# ECAT_RJ45.net
KiCad netlist of a schematic drawn in Altium Designer
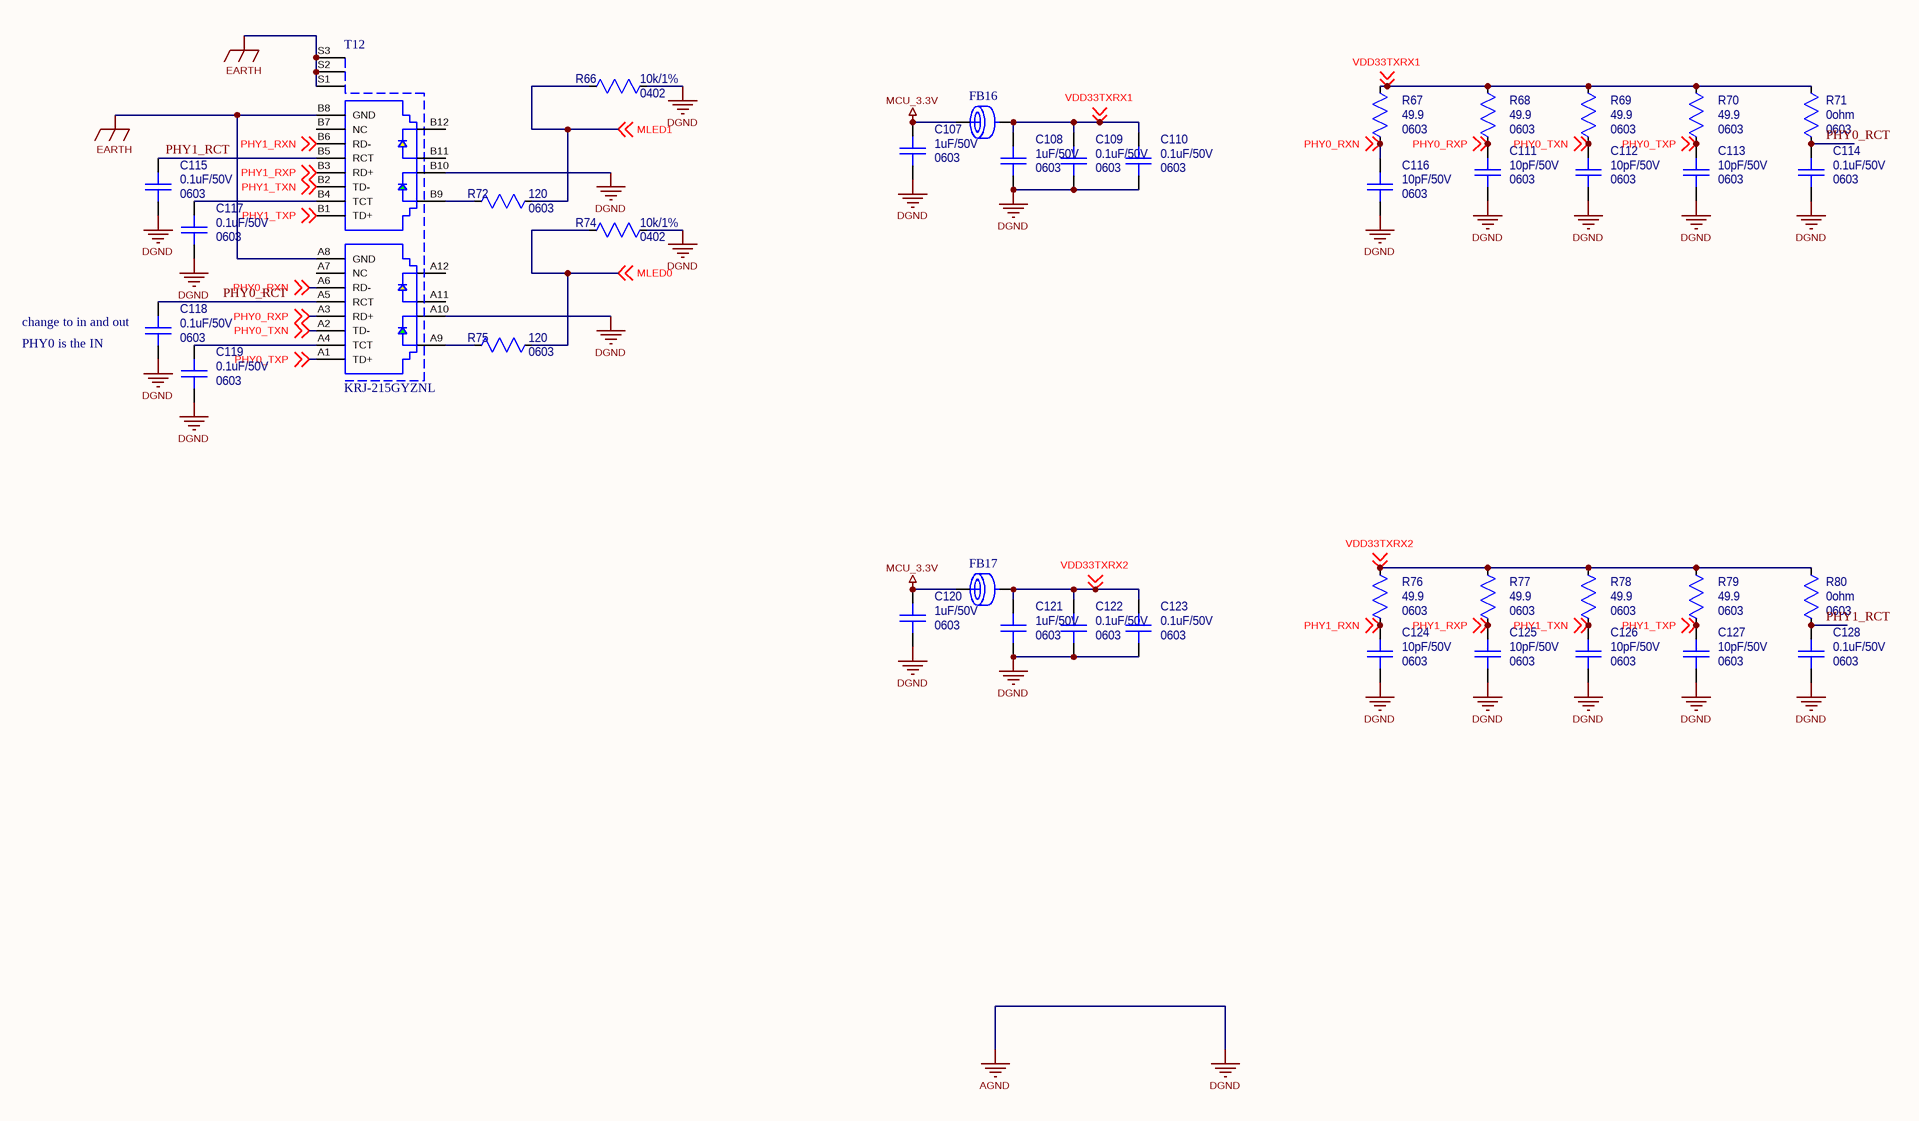
[diagram p0: ECAT RJ45.SchDoc]

(export (version "E")
  (design (tool "Eeschema 10.0.6"))
  (components
    (comp (ref "C107")
      (value "1uF/50V")
      (footprint "CAPC1608X092N_0603")
      (fields
        (field (name "PARTNUMBER") "CL10A105KB8NNNC")
        (field (name "TOLERANCE") "[tol]")
        (field (name "PACKAGE") "0603")
      )
      (libsource (lib "Karl") (part "Capacitor_0603"))
    )
    (comp (ref "C108")
      (value "1uF/50V")
      (footprint "CAPC1608X092N_0603")
      (fields
        (field (name "PARTNUMBER") "CL10A105KB8NNNC")
        (field (name "TOLERANCE") "[tol]")
        (field (name "PACKAGE") "0603")
      )
      (libsource (lib "Karl") (part "Capacitor_0603"))
    )
    (comp (ref "C109")
      (value "0.1uF/50V")
      (footprint "CAPC1608X092N_0603")
      (fields
        (field (name "PARTNUMBER") "CC0603KRX7R9BB104")
        (field (name "TOLERANCE") "[tol]")
        (field (name "PACKAGE") "0603")
      )
      (libsource (lib "Karl") (part "Capacitor_0402"))
    )
    (comp (ref "C110")
      (value "0.1uF/50V")
      (footprint "CAPC1608X092N_0603")
      (fields
        (field (name "PARTNUMBER") "CC0603KRX7R9BB104")
        (field (name "TOLERANCE") "[tol]")
        (field (name "PACKAGE") "0603")
      )
      (libsource (lib "Karl") (part "Capacitor_0402"))
    )
    (comp (ref "C111")
      (value "10pF/50V")
      (footprint "CAPC1608X092N_0603")
      (fields
        (field (name "PARTNUMBER") "CC0603JRNPO9BN100")
        (field (name "TOLERANCE") "[tol]")
        (field (name "PACKAGE") "0603")
      )
      (libsource (lib "Karl") (part "Capacitor_0603"))
    )
    (comp (ref "C112")
      (value "10pF/50V")
      (footprint "CAPC1608X092N_0603")
      (fields
        (field (name "PARTNUMBER") "CC0603JRNPO9BN100")
        (field (name "TOLERANCE") "[tol]")
        (field (name "PACKAGE") "0603")
      )
      (libsource (lib "Karl") (part "Capacitor_0603"))
    )
    (comp (ref "C113")
      (value "10pF/50V")
      (footprint "CAPC1608X092N_0603")
      (fields
        (field (name "PARTNUMBER") "CC0603JRNPO9BN100")
        (field (name "TOLERANCE") "[tol]")
        (field (name "PACKAGE") "0603")
      )
      (libsource (lib "Karl") (part "Capacitor_0603"))
    )
    (comp (ref "C114")
      (value "0.1uF/50V")
      (footprint "CAPC1608X092N_0603")
      (fields
        (field (name "PARTNUMBER") "CC0603KRX7R9BB104")
        (field (name "TOLERANCE") "[tol]")
        (field (name "PACKAGE") "0603")
      )
      (libsource (lib "Karl") (part "Capacitor_0402"))
    )
    (comp (ref "C115")
      (value "0.1uF/50V")
      (footprint "CAPC1608X092N_0603")
      (fields
        (field (name "PARTNUMBER") "CC0603KRX7R9BB104")
        (field (name "TOLERANCE") "[tol]")
        (field (name "PACKAGE") "0603")
      )
      (libsource (lib "Karl") (part "Capacitor_0603"))
    )
    (comp (ref "C116")
      (value "10pF/50V")
      (footprint "CAPC1608X092N_0603")
      (fields
        (field (name "PARTNUMBER") "CC0603JRNPO9BN100")
        (field (name "TOLERANCE") "[tol]")
        (field (name "PACKAGE") "0603")
      )
      (libsource (lib "Karl") (part "Capacitor_0603"))
    )
    (comp (ref "C117")
      (value "0.1uF/50V")
      (footprint "CAPC1608X092N_0603")
      (fields
        (field (name "PARTNUMBER") "CC0603KRX7R9BB104")
        (field (name "TOLERANCE") "[tol]")
        (field (name "PACKAGE") "0603")
      )
      (libsource (lib "Karl") (part "Capacitor_0603"))
    )
    (comp (ref "C118")
      (value "0.1uF/50V")
      (footprint "CAPC1608X092N_0603")
      (fields
        (field (name "PARTNUMBER") "CC0603KRX7R9BB104")
        (field (name "TOLERANCE") "[tol]")
        (field (name "PACKAGE") "0603")
      )
      (libsource (lib "Karl") (part "Capacitor_0603"))
    )
    (comp (ref "C119")
      (value "0.1uF/50V")
      (footprint "CAPC1608X092N_0603")
      (fields
        (field (name "PARTNUMBER") "CC0603KRX7R9BB104")
        (field (name "TOLERANCE") "[tol]")
        (field (name "PACKAGE") "0603")
      )
      (libsource (lib "Karl") (part "Capacitor_0603"))
    )
    (comp (ref "C120")
      (value "1uF/50V")
      (footprint "CAPC1608X092N_0603")
      (fields
        (field (name "PARTNUMBER") "CL10A105KB8NNNC")
        (field (name "TOLERANCE") "[tol]")
        (field (name "PACKAGE") "0603")
      )
      (libsource (lib "Karl") (part "Capacitor_0603"))
    )
    (comp (ref "C121")
      (value "1uF/50V")
      (footprint "CAPC1608X092N_0603")
      (fields
        (field (name "PARTNUMBER") "CL10A105KB8NNNC")
        (field (name "TOLERANCE") "[tol]")
        (field (name "PACKAGE") "0603")
      )
      (libsource (lib "Karl") (part "Capacitor_0603"))
    )
    (comp (ref "C122")
      (value "0.1uF/50V")
      (footprint "CAPC1608X092N_0603")
      (fields
        (field (name "PARTNUMBER") "CC0603KRX7R9BB104")
        (field (name "TOLERANCE") "[tol]")
        (field (name "PACKAGE") "0603")
      )
      (libsource (lib "Karl") (part "Capacitor_0402"))
    )
    (comp (ref "C123")
      (value "0.1uF/50V")
      (footprint "CAPC1608X092N_0603")
      (fields
        (field (name "PARTNUMBER") "CC0603KRX7R9BB104")
        (field (name "TOLERANCE") "[tol]")
        (field (name "PACKAGE") "0603")
      )
      (libsource (lib "Karl") (part "Capacitor_0402"))
    )
    (comp (ref "C124")
      (value "10pF/50V")
      (footprint "CAPC1608X092N_0603")
      (fields
        (field (name "PARTNUMBER") "CC0603JRNPO9BN100")
        (field (name "TOLERANCE") "[tol]")
        (field (name "PACKAGE") "0603")
      )
      (libsource (lib "Karl") (part "Capacitor_0603"))
    )
    (comp (ref "C125")
      (value "10pF/50V")
      (footprint "CAPC1608X092N_0603")
      (fields
        (field (name "PARTNUMBER") "CC0603JRNPO9BN100")
        (field (name "TOLERANCE") "[tol]")
        (field (name "PACKAGE") "0603")
      )
      (libsource (lib "Karl") (part "Capacitor_0603"))
    )
    (comp (ref "C126")
      (value "10pF/50V")
      (footprint "CAPC1608X092N_0603")
      (fields
        (field (name "PARTNUMBER") "CC0603JRNPO9BN100")
        (field (name "TOLERANCE") "[tol]")
        (field (name "PACKAGE") "0603")
      )
      (libsource (lib "Karl") (part "Capacitor_0603"))
    )
    (comp (ref "C127")
      (value "10pF/50V")
      (footprint "CAPC1608X092N_0603")
      (fields
        (field (name "PARTNUMBER") "CC0603JRNPO9BN100")
        (field (name "TOLERANCE") "[tol]")
        (field (name "PACKAGE") "0603")
      )
      (libsource (lib "Karl") (part "Capacitor_0603"))
    )
    (comp (ref "C128")
      (value "0.1uF/50V")
      (footprint "CAPC1608X092N_0603")
      (fields
        (field (name "PARTNUMBER") "CC0603KRX7R9BB104")
        (field (name "TOLERANCE") "[tol]")
        (field (name "PACKAGE") "0603")
      )
      (libsource (lib "Karl") (part "Capacitor_0402"))
    )
    (comp (ref "FB16")
      (value "FBC0603")
      (footprint "FBC0603")
      (fields (field (name "PARTNUMBER") "BLM18AG601SN1D"))
      (libsource (lib "Karl") (part "FBC0603"))
    )
    (comp (ref "FB17")
      (value "FBC0603")
      (footprint "FBC0603")
      (fields (field (name "PARTNUMBER") "BLM18AG601SN1D"))
      (libsource (lib "Karl") (part "FBC0603"))
    )
    (comp (ref "R66")
      (value "10k/1%")
      (footprint "RESC1005X040N_0402")
      (fields
        (field (name "PARTNUMBER") "MR04X1002FTL")
        (field (name "TOLERANCE") "tol")
        (field (name "PACKAGE") "0402")
      )
      (libsource (lib "Karl") (part "Resistor_0402"))
    )
    (comp (ref "R67")
      (value "49.9")
      (footprint "RESC1608X055N_0603")
      (fields
        (field (name "PARTNUMBER") "0603WAF499JT5E")
        (field (name "TOLERANCE") "tol")
        (field (name "PACKAGE") "0603")
      )
      (libsource (lib "Karl") (part "Resistor_0603"))
    )
    (comp (ref "R68")
      (value "49.9")
      (footprint "RESC1608X055N_0603")
      (fields
        (field (name "PARTNUMBER") "0603WAF499JT5E")
        (field (name "TOLERANCE") "tol")
        (field (name "PACKAGE") "0603")
      )
      (libsource (lib "Karl") (part "Resistor_0603"))
    )
    (comp (ref "R69")
      (value "49.9")
      (footprint "RESC1608X055N_0603")
      (fields
        (field (name "PARTNUMBER") "0603WAF499JT5E")
        (field (name "TOLERANCE") "tol")
        (field (name "PACKAGE") "0603")
      )
      (libsource (lib "Karl") (part "Resistor_0603"))
    )
    (comp (ref "R70")
      (value "49.9")
      (footprint "RESC1608X055N_0603")
      (fields
        (field (name "PARTNUMBER") "0603WAF499JT5E")
        (field (name "TOLERANCE") "tol")
        (field (name "PACKAGE") "0603")
      )
      (libsource (lib "Karl") (part "Resistor_0603"))
    )
    (comp (ref "R71")
      (value "0ohm")
      (footprint "RESC1608X055N_0603")
      (fields
        (field (name "PARTNUMBER") "RC0603JR-070RL")
        (field (name "TOLERANCE") "tol")
        (field (name "PACKAGE") "0603")
      )
      (libsource (lib "Karl") (part "Resistor_0603"))
    )
    (comp (ref "R72")
      (value "120")
      (footprint "RESC1608X055N_0603")
      (fields
        (field (name "PARTNUMBER") "RC0603FR-07120RL")
        (field (name "TOLERANCE") "tol")
        (field (name "PACKAGE") "0603")
      )
      (libsource (lib "Karl") (part "Resistor_0603"))
    )
    (comp (ref "R74")
      (value "10k/1%")
      (footprint "RESC1005X040N_0402")
      (fields
        (field (name "PARTNUMBER") "MR04X1002FTL")
        (field (name "TOLERANCE") "tol")
        (field (name "PACKAGE") "0402")
      )
      (libsource (lib "Karl") (part "Resistor_0402"))
    )
    (comp (ref "R75")
      (value "120")
      (footprint "RESC1608X055N_0603")
      (fields
        (field (name "PARTNUMBER") "RC0603FR-07120RL")
        (field (name "TOLERANCE") "tol")
        (field (name "PACKAGE") "0603")
      )
      (libsource (lib "Karl") (part "Resistor_0603"))
    )
    (comp (ref "R76")
      (value "49.9")
      (footprint "RESC1608X055N_0603")
      (fields
        (field (name "PARTNUMBER") "0603WAF499JT5E")
        (field (name "TOLERANCE") "tol")
        (field (name "PACKAGE") "0603")
      )
      (libsource (lib "Karl") (part "Resistor_0603"))
    )
    (comp (ref "R77")
      (value "49.9")
      (footprint "RESC1608X055N_0603")
      (fields
        (field (name "PARTNUMBER") "0603WAF499JT5E")
        (field (name "TOLERANCE") "tol")
        (field (name "PACKAGE") "0603")
      )
      (libsource (lib "Karl") (part "Resistor_0603"))
    )
    (comp (ref "R78")
      (value "49.9")
      (footprint "RESC1608X055N_0603")
      (fields
        (field (name "PARTNUMBER") "0603WAF499JT5E")
        (field (name "TOLERANCE") "tol")
        (field (name "PACKAGE") "0603")
      )
      (libsource (lib "Karl") (part "Resistor_0603"))
    )
    (comp (ref "R79")
      (value "49.9")
      (footprint "RESC1608X055N_0603")
      (fields
        (field (name "PARTNUMBER") "0603WAF499JT5E")
        (field (name "TOLERANCE") "tol")
        (field (name "PACKAGE") "0603")
      )
      (libsource (lib "Karl") (part "Resistor_0603"))
    )
    (comp (ref "R80")
      (value "0ohm")
      (footprint "RESC1608X055N_0603")
      (fields
        (field (name "PARTNUMBER") "RC0603JR-070RL")
        (field (name "TOLERANCE") "tol")
        (field (name "PACKAGE") "0603")
      )
      (libsource (lib "Karl") (part "Resistor_0603"))
    )
    (comp (ref "T12")
      (value "KRJ-215GYZNL")
      (footprint "DGKYD-KRJ-211_V")
      (fields (field (name "PART NUMBER") "KRJ-211GYNL") (field (name "PUBLISHER") "DGKYD"))
      (libsource (lib "Bogen") (part "KRJ-215GYZNL"))
    )
  )
  (nets
    (net (code "1") (name "/PHY0_RCT") (class "Default")
      (node (ref "C114") (pin "1") (pinfunction "1_1") (pintype "passive"))
      (node (ref "C118") (pin "1") (pinfunction "1_1") (pintype "passive"))
      (node (ref "R71") (pin "2") (pinfunction "2_2") (pintype "passive"))
      (node (ref "T12") (pin "A5") (pinfunction "RCT_A5") (pintype "passive"))
    )
    (net (code "2") (name "/PHY1_RCT") (class "Default")
      (node (ref "C115") (pin "1") (pinfunction "1_1") (pintype "passive"))
      (node (ref "C128") (pin "1") (pinfunction "1_1") (pintype "passive"))
      (node (ref "R80") (pin "2") (pinfunction "2_2") (pintype "passive"))
      (node (ref "T12") (pin "B5") (pinfunction "RCT_B5") (pintype "passive"))
    )
    (net (code "3") (name "AGND") (class "Default")
      (node (ref "C107") (pin "2") (pinfunction "2_2") (pintype "passive"))
      (node (ref "C108") (pin "2") (pinfunction "2_2") (pintype "passive"))
      (node (ref "C109") (pin "2") (pinfunction "2_2") (pintype "passive"))
      (node (ref "C110") (pin "2") (pinfunction "2_2") (pintype "passive"))
      (node (ref "C111") (pin "2") (pinfunction "2_2") (pintype "passive"))
      (node (ref "C112") (pin "2") (pinfunction "2_2") (pintype "passive"))
      (node (ref "C113") (pin "2") (pinfunction "2_2") (pintype "passive"))
      (node (ref "C114") (pin "2") (pinfunction "2_2") (pintype "passive"))
      (node (ref "C115") (pin "2") (pinfunction "2_2") (pintype "passive"))
      (node (ref "C116") (pin "2") (pinfunction "2_2") (pintype "passive"))
      (node (ref "C117") (pin "2") (pinfunction "2_2") (pintype "passive"))
      (node (ref "C118") (pin "2") (pinfunction "2_2") (pintype "passive"))
      (node (ref "C119") (pin "2") (pinfunction "2_2") (pintype "passive"))
      (node (ref "C120") (pin "2") (pinfunction "2_2") (pintype "passive"))
      (node (ref "C121") (pin "2") (pinfunction "2_2") (pintype "passive"))
      (node (ref "C122") (pin "2") (pinfunction "2_2") (pintype "passive"))
      (node (ref "C123") (pin "2") (pinfunction "2_2") (pintype "passive"))
      (node (ref "C124") (pin "2") (pinfunction "2_2") (pintype "passive"))
      (node (ref "C125") (pin "2") (pinfunction "2_2") (pintype "passive"))
      (node (ref "C126") (pin "2") (pinfunction "2_2") (pintype "passive"))
      (node (ref "C127") (pin "2") (pinfunction "2_2") (pintype "passive"))
      (node (ref "C128") (pin "2") (pinfunction "2_2") (pintype "passive"))
      (node (ref "R66") (pin "1") (pinfunction "1_1") (pintype "passive"))
      (node (ref "R74") (pin "1") (pinfunction "1_1") (pintype "passive"))
      (node (ref "T12") (pin "A10") (pinfunction "A10_A10") (pintype "passive"))
      (node (ref "T12") (pin "B10") (pinfunction "B10_B10") (pintype "passive"))
    )
    (net (code "4") (name "EARTH") (class "Default")
      (node (ref "T12") (pin "A8") (pinfunction "GND_A8") (pintype "passive"))
      (node (ref "T12") (pin "B8") (pinfunction "GND_B8") (pintype "passive"))
      (node (ref "T12") (pin "S1") (pinfunction "Shield_S1") (pintype "passive"))
      (node (ref "T12") (pin "S2") (pinfunction "Shield_S2") (pintype "passive"))
      (node (ref "T12") (pin "S3") (pinfunction "Shield_S3") (pintype "passive"))
    )
    (net (code "5") (name "MCU_3.3V") (class "Default")
      (node (ref "C107") (pin "1") (pinfunction "1_1") (pintype "passive"))
      (node (ref "C120") (pin "1") (pinfunction "1_1") (pintype "passive"))
      (node (ref "FB16") (pin "1") (pinfunction "1_1") (pintype "passive"))
      (node (ref "FB17") (pin "1") (pinfunction "1_1") (pintype "passive"))
    )
    (net (code "6") (name "MLED0") (class "Default")
      (node (ref "R74") (pin "2") (pinfunction "2_2") (pintype "passive"))
      (node (ref "R75") (pin "1") (pinfunction "1_1") (pintype "passive"))
    )
    (net (code "7") (name "MLED1") (class "Default")
      (node (ref "R66") (pin "2") (pinfunction "2_2") (pintype "passive"))
      (node (ref "R72") (pin "1") (pinfunction "1_1") (pintype "passive"))
    )
    (net (code "8") (name "Net-(C117-Pad1)") (class "Default")
      (node (ref "C117") (pin "1") (pinfunction "1_1") (pintype "passive"))
      (node (ref "T12") (pin "B4") (pinfunction "TCT_B4") (pintype "passive"))
    )
    (net (code "9") (name "Net-(C119-Pad1)") (class "Default")
      (node (ref "C119") (pin "1") (pinfunction "1_1") (pintype "passive"))
      (node (ref "T12") (pin "A4") (pinfunction "TCT_A4") (pintype "passive"))
    )
    (net (code "10") (name "Net-(R72-Pad2)") (class "Default")
      (node (ref "R72") (pin "2") (pinfunction "2_2") (pintype "passive"))
      (node (ref "T12") (pin "B9") (pinfunction "B9_B9") (pintype "passive"))
    )
    (net (code "11") (name "Net-(R75-Pad2)") (class "Default")
      (node (ref "R75") (pin "2") (pinfunction "2_2") (pintype "passive"))
      (node (ref "T12") (pin "A9") (pinfunction "A9_A9") (pintype "passive"))
    )
    (net (code "12") (name "PHY0_RXN") (class "Default")
      (node (ref "C116") (pin "1") (pinfunction "1_1") (pintype "passive"))
      (node (ref "R67") (pin "1") (pinfunction "1_1") (pintype "passive"))
      (node (ref "T12") (pin "A6") (pinfunction "RD-_A6") (pintype "passive"))
    )
    (net (code "13") (name "PHY0_RXP") (class "Default")
      (node (ref "C111") (pin "1") (pinfunction "1_1") (pintype "passive"))
      (node (ref "R68") (pin "1") (pinfunction "1_1") (pintype "passive"))
      (node (ref "T12") (pin "A3") (pinfunction "RD+_A3") (pintype "passive"))
    )
    (net (code "14") (name "PHY0_TXN") (class "Default")
      (node (ref "C112") (pin "1") (pinfunction "1_1") (pintype "passive"))
      (node (ref "R69") (pin "1") (pinfunction "1_1") (pintype "passive"))
      (node (ref "T12") (pin "A2") (pinfunction "TD-_A2") (pintype "passive"))
    )
    (net (code "15") (name "PHY0_TXP") (class "Default")
      (node (ref "C113") (pin "1") (pinfunction "1_1") (pintype "passive"))
      (node (ref "R70") (pin "1") (pinfunction "1_1") (pintype "passive"))
      (node (ref "T12") (pin "A1") (pinfunction "TD+_A1") (pintype "passive"))
    )
    (net (code "16") (name "PHY1_RXN") (class "Default")
      (node (ref "C124") (pin "1") (pinfunction "1_1") (pintype "passive"))
      (node (ref "R76") (pin "1") (pinfunction "1_1") (pintype "passive"))
      (node (ref "T12") (pin "B6") (pinfunction "RD-_B6") (pintype "passive"))
    )
    (net (code "17") (name "PHY1_RXP") (class "Default")
      (node (ref "C125") (pin "1") (pinfunction "1_1") (pintype "passive"))
      (node (ref "R77") (pin "1") (pinfunction "1_1") (pintype "passive"))
      (node (ref "T12") (pin "B3") (pinfunction "RD+_B3") (pintype "passive"))
    )
    (net (code "18") (name "PHY1_TXN") (class "Default")
      (node (ref "C126") (pin "1") (pinfunction "1_1") (pintype "passive"))
      (node (ref "R78") (pin "1") (pinfunction "1_1") (pintype "passive"))
      (node (ref "T12") (pin "B2") (pinfunction "TD-_B2") (pintype "passive"))
    )
    (net (code "19") (name "PHY1_TXP") (class "Default")
      (node (ref "C127") (pin "1") (pinfunction "1_1") (pintype "passive"))
      (node (ref "R79") (pin "1") (pinfunction "1_1") (pintype "passive"))
      (node (ref "T12") (pin "B1") (pinfunction "TD+_B1") (pintype "passive"))
    )
    (net (code "20") (name "VDD33TXRX1") (class "Default")
      (node (ref "C108") (pin "1") (pinfunction "1_1") (pintype "passive"))
      (node (ref "C109") (pin "1") (pinfunction "1_1") (pintype "passive"))
      (node (ref "C110") (pin "1") (pinfunction "1_1") (pintype "passive"))
      (node (ref "FB16") (pin "2") (pinfunction "2_2") (pintype "passive"))
      (node (ref "R67") (pin "2") (pinfunction "2_2") (pintype "passive"))
      (node (ref "R68") (pin "2") (pinfunction "2_2") (pintype "passive"))
      (node (ref "R69") (pin "2") (pinfunction "2_2") (pintype "passive"))
      (node (ref "R70") (pin "2") (pinfunction "2_2") (pintype "passive"))
      (node (ref "R71") (pin "1") (pinfunction "1_1") (pintype "passive"))
    )
    (net (code "21") (name "VDD33TXRX2") (class "Default")
      (node (ref "C121") (pin "1") (pinfunction "1_1") (pintype "passive"))
      (node (ref "C122") (pin "1") (pinfunction "1_1") (pintype "passive"))
      (node (ref "C123") (pin "1") (pinfunction "1_1") (pintype "passive"))
      (node (ref "FB17") (pin "2") (pinfunction "2_2") (pintype "passive"))
      (node (ref "R76") (pin "2") (pinfunction "2_2") (pintype "passive"))
      (node (ref "R77") (pin "2") (pinfunction "2_2") (pintype "passive"))
      (node (ref "R78") (pin "2") (pinfunction "2_2") (pintype "passive"))
      (node (ref "R79") (pin "2") (pinfunction "2_2") (pintype "passive"))
      (node (ref "R80") (pin "1") (pinfunction "1_1") (pintype "passive"))
    )
    (net (code "22") (name "unconnected-(T12-NC-PadA7)") (class "Default")
      (node (ref "T12") (pin "A7") (pinfunction "NC_A7") (pintype "passive"))
    )
    (net (code "23") (name "unconnected-(T12-NC-PadB7)") (class "Default")
      (node (ref "T12") (pin "B7") (pinfunction "NC_B7") (pintype "passive"))
    )
    (net (code "24") (name "unconnected-(T12-PadA11)") (class "Default")
      (node (ref "T12") (pin "A11") (pinfunction "A11_A11") (pintype "passive"))
    )
    (net (code "25") (name "unconnected-(T12-PadA12)") (class "Default")
      (node (ref "T12") (pin "A12") (pinfunction "A12_A12") (pintype "passive"))
    )
    (net (code "26") (name "unconnected-(T12-PadB11)") (class "Default")
      (node (ref "T12") (pin "B11") (pinfunction "B11_B11") (pintype "passive"))
    )
    (net (code "27") (name "unconnected-(T12-PadB12)") (class "Default")
      (node (ref "T12") (pin "B12") (pinfunction "B12_B12") (pintype "passive"))
    )
  )
)
